# 2022-01-19_AD590_HIH-4031.net
KiCad netlist of a schematic drawn in EAGLE
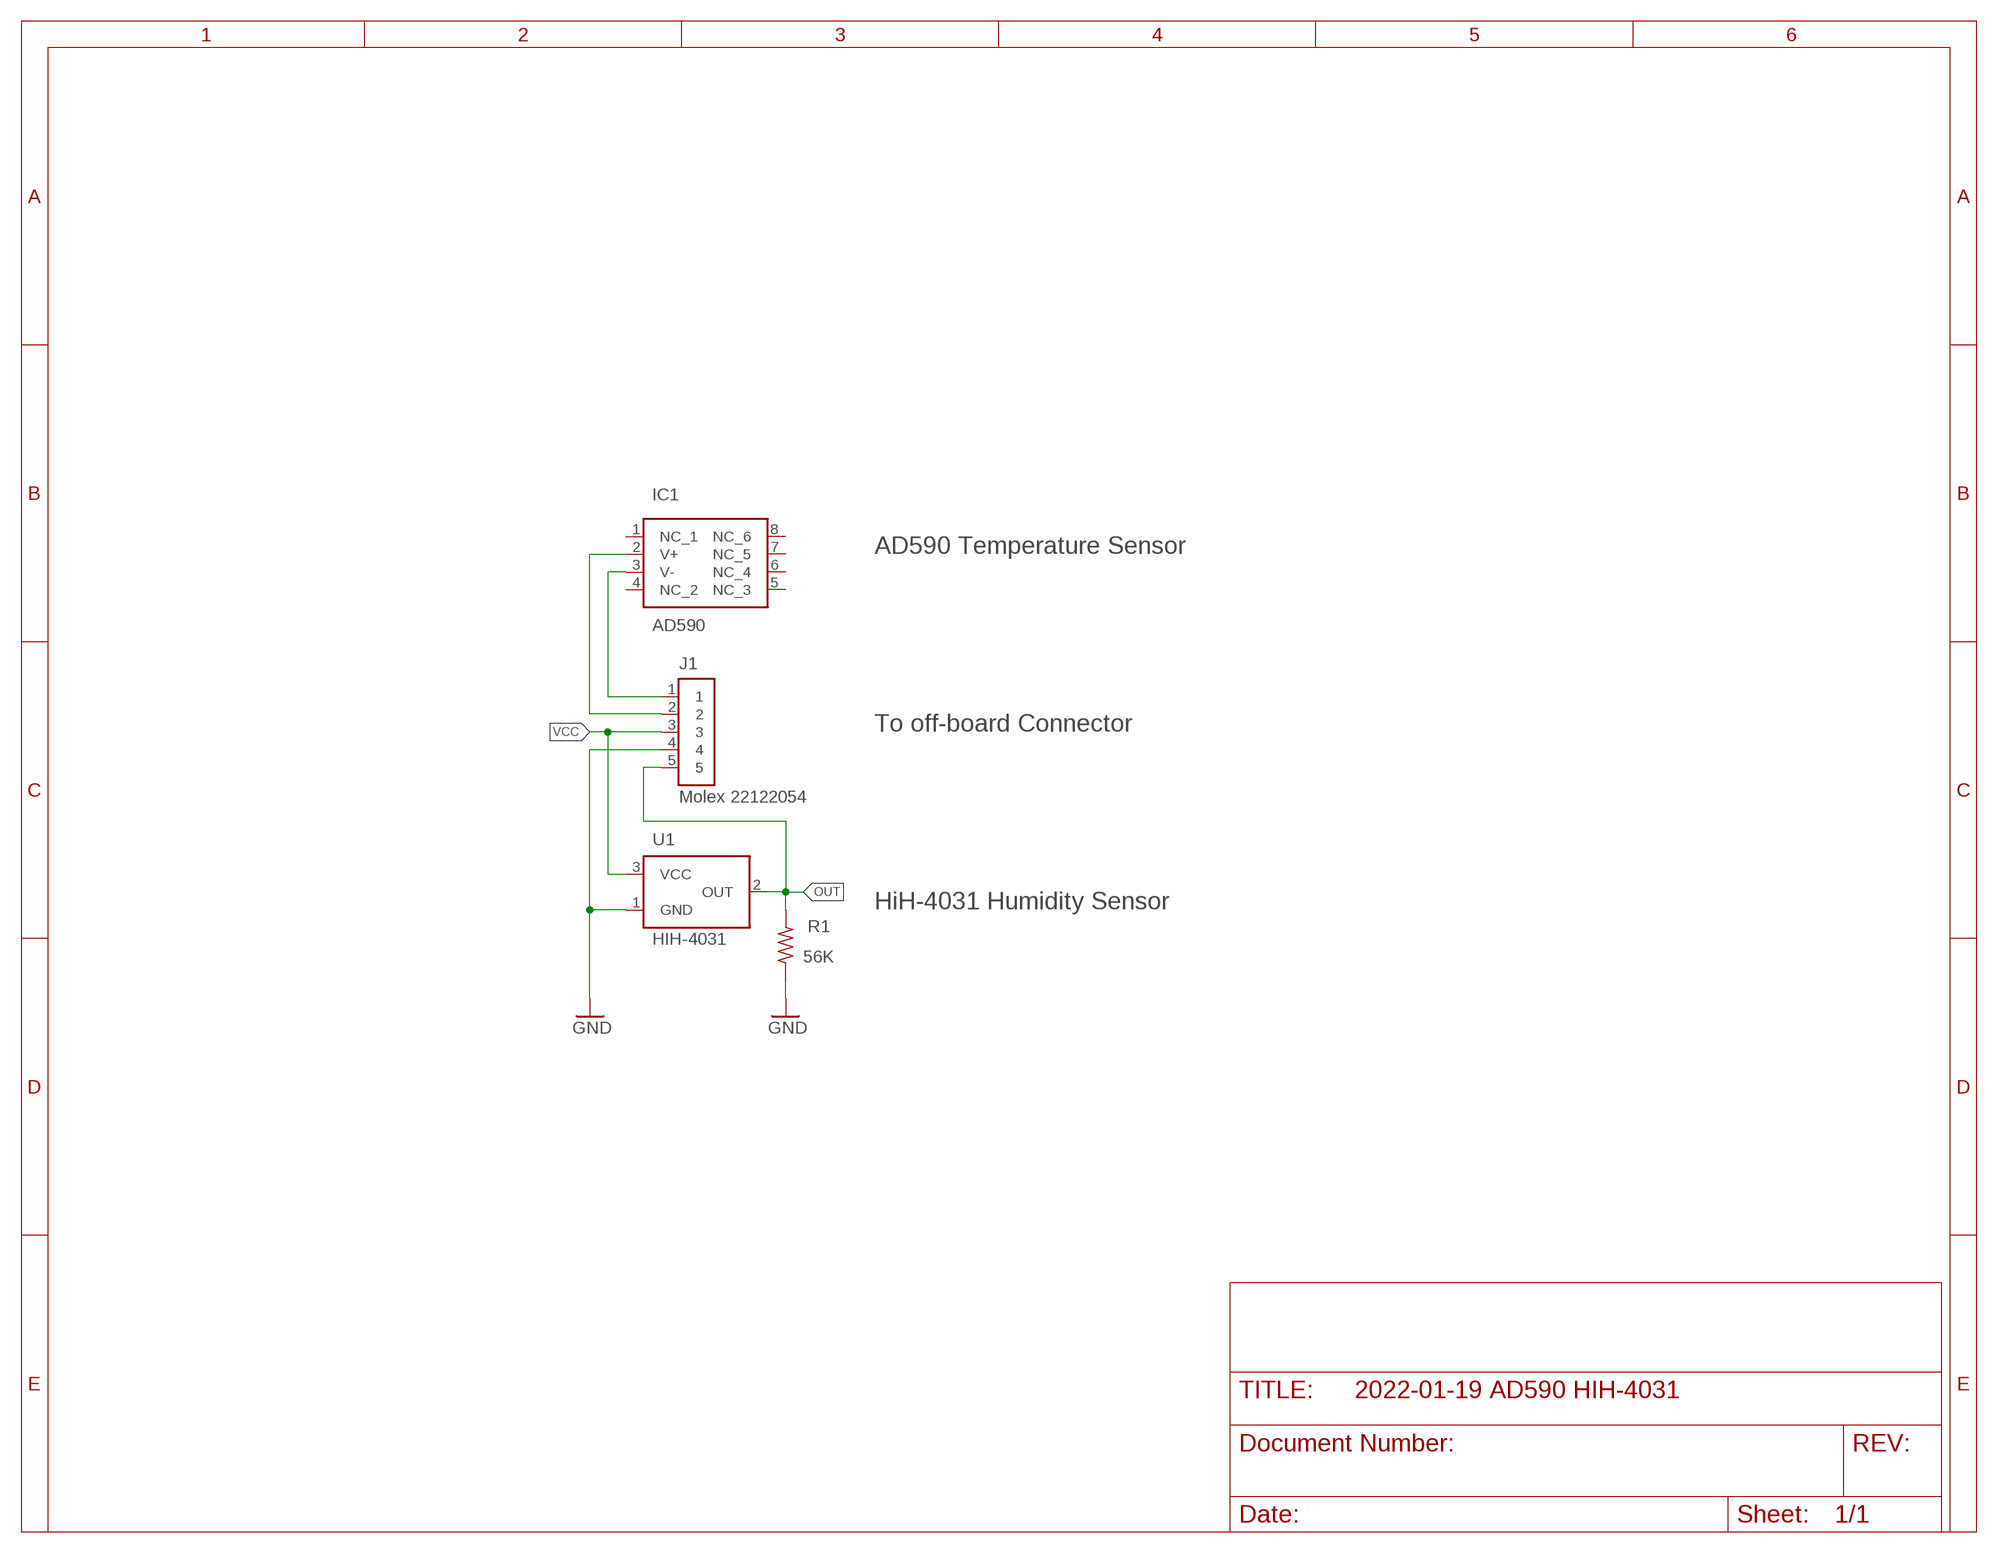
[diagram p0: schematic, sheet 1]

(export (version "E")
  (design (tool "Eeschema 10.0.6"))
  (components
    (comp (ref "IC1")
      (value "AD590")
      (footprint "eagle-import:SOIC127P600X175-8N")
      (fields
        (field (name "MANUFACTURER_PART_NUMBER") "AD590JRZ")
        (field (name "MOUSER_PART_NUMBER") "584-AD590JRZ")
        (field (name "RS_PART_NUMBER") "7096005P")
      )
      (libsource (lib "eagle-import") (part "AD590JRZ"))
    )
    (comp (ref "J1")
      (value "Molex 22122054")
      (footprint "eagle-import:1X05RA-MOLEX-22122054")
      (libsource (lib "eagle-import") (part "PINHD-1X5RA-MOLEX-22122054"))
    )
    (comp (ref "R1")
      (value "56K")
      (footprint "eagle-import:R0805")
      (libsource (lib "eagle-import") (part "R-US_R0805"))
    )
    (comp (ref "U1")
      (value "HIH-4031")
      (footprint "eagle-import:HIH-4030")
      (libsource (lib "eagle-import") (part "HIH-4030"))
    )
  )
  (nets
    (net (code "1") (name "GND") (class "Default")
      (node (ref "J1") (pin "4") (pinfunction "4_4") (pintype "bidirectional"))
      (node (ref "R1") (pin "1") (pinfunction "1_1") (pintype "passive"))
      (node (ref "U1") (pin "1") (pinfunction "GND_1") (pintype "bidirectional"))
    )
    (net (code "2") (name "Net-(IC1-V+)") (class "Default")
      (node (ref "IC1") (pin "2") (pinfunction "V+_2") (pintype "bidirectional"))
      (node (ref "J1") (pin "2") (pinfunction "2_2") (pintype "bidirectional"))
    )
    (net (code "3") (name "Net-(IC1-V-)") (class "Default")
      (node (ref "IC1") (pin "3") (pinfunction "V-_3") (pintype "bidirectional"))
      (node (ref "J1") (pin "1") (pinfunction "1_1") (pintype "bidirectional"))
    )
    (net (code "4") (name "OUT") (class "Default")
      (node (ref "J1") (pin "5") (pinfunction "5_5") (pintype "bidirectional"))
      (node (ref "R1") (pin "2") (pinfunction "2_2") (pintype "passive"))
      (node (ref "U1") (pin "2") (pinfunction "OUT_2") (pintype "bidirectional"))
    )
    (net (code "5") (name "VCC") (class "Default")
      (node (ref "J1") (pin "3") (pinfunction "3_3") (pintype "bidirectional"))
      (node (ref "U1") (pin "3") (pinfunction "VCC_3") (pintype "bidirectional"))
    )
    (net (code "6") (name "unconnected-(IC1-NC_1-Pad1)") (class "Default")
      (node (ref "IC1") (pin "1") (pinfunction "NC_1_1") (pintype "bidirectional"))
    )
    (net (code "7") (name "unconnected-(IC1-NC_2-Pad4)") (class "Default")
      (node (ref "IC1") (pin "4") (pinfunction "NC_2_4") (pintype "bidirectional"))
    )
    (net (code "8") (name "unconnected-(IC1-NC_3-Pad5)") (class "Default")
      (node (ref "IC1") (pin "5") (pinfunction "NC_3_5") (pintype "bidirectional"))
    )
    (net (code "9") (name "unconnected-(IC1-NC_4-Pad6)") (class "Default")
      (node (ref "IC1") (pin "6") (pinfunction "NC_4_6") (pintype "bidirectional"))
    )
    (net (code "10") (name "unconnected-(IC1-NC_5-Pad7)") (class "Default")
      (node (ref "IC1") (pin "7") (pinfunction "NC_5_7") (pintype "bidirectional"))
    )
    (net (code "11") (name "unconnected-(IC1-NC_6-Pad8)") (class "Default")
      (node (ref "IC1") (pin "8") (pinfunction "NC_6_8") (pintype "bidirectional"))
    )
  )
)
